# IO.net
KiCad netlist of a schematic drawn in Altium Designer
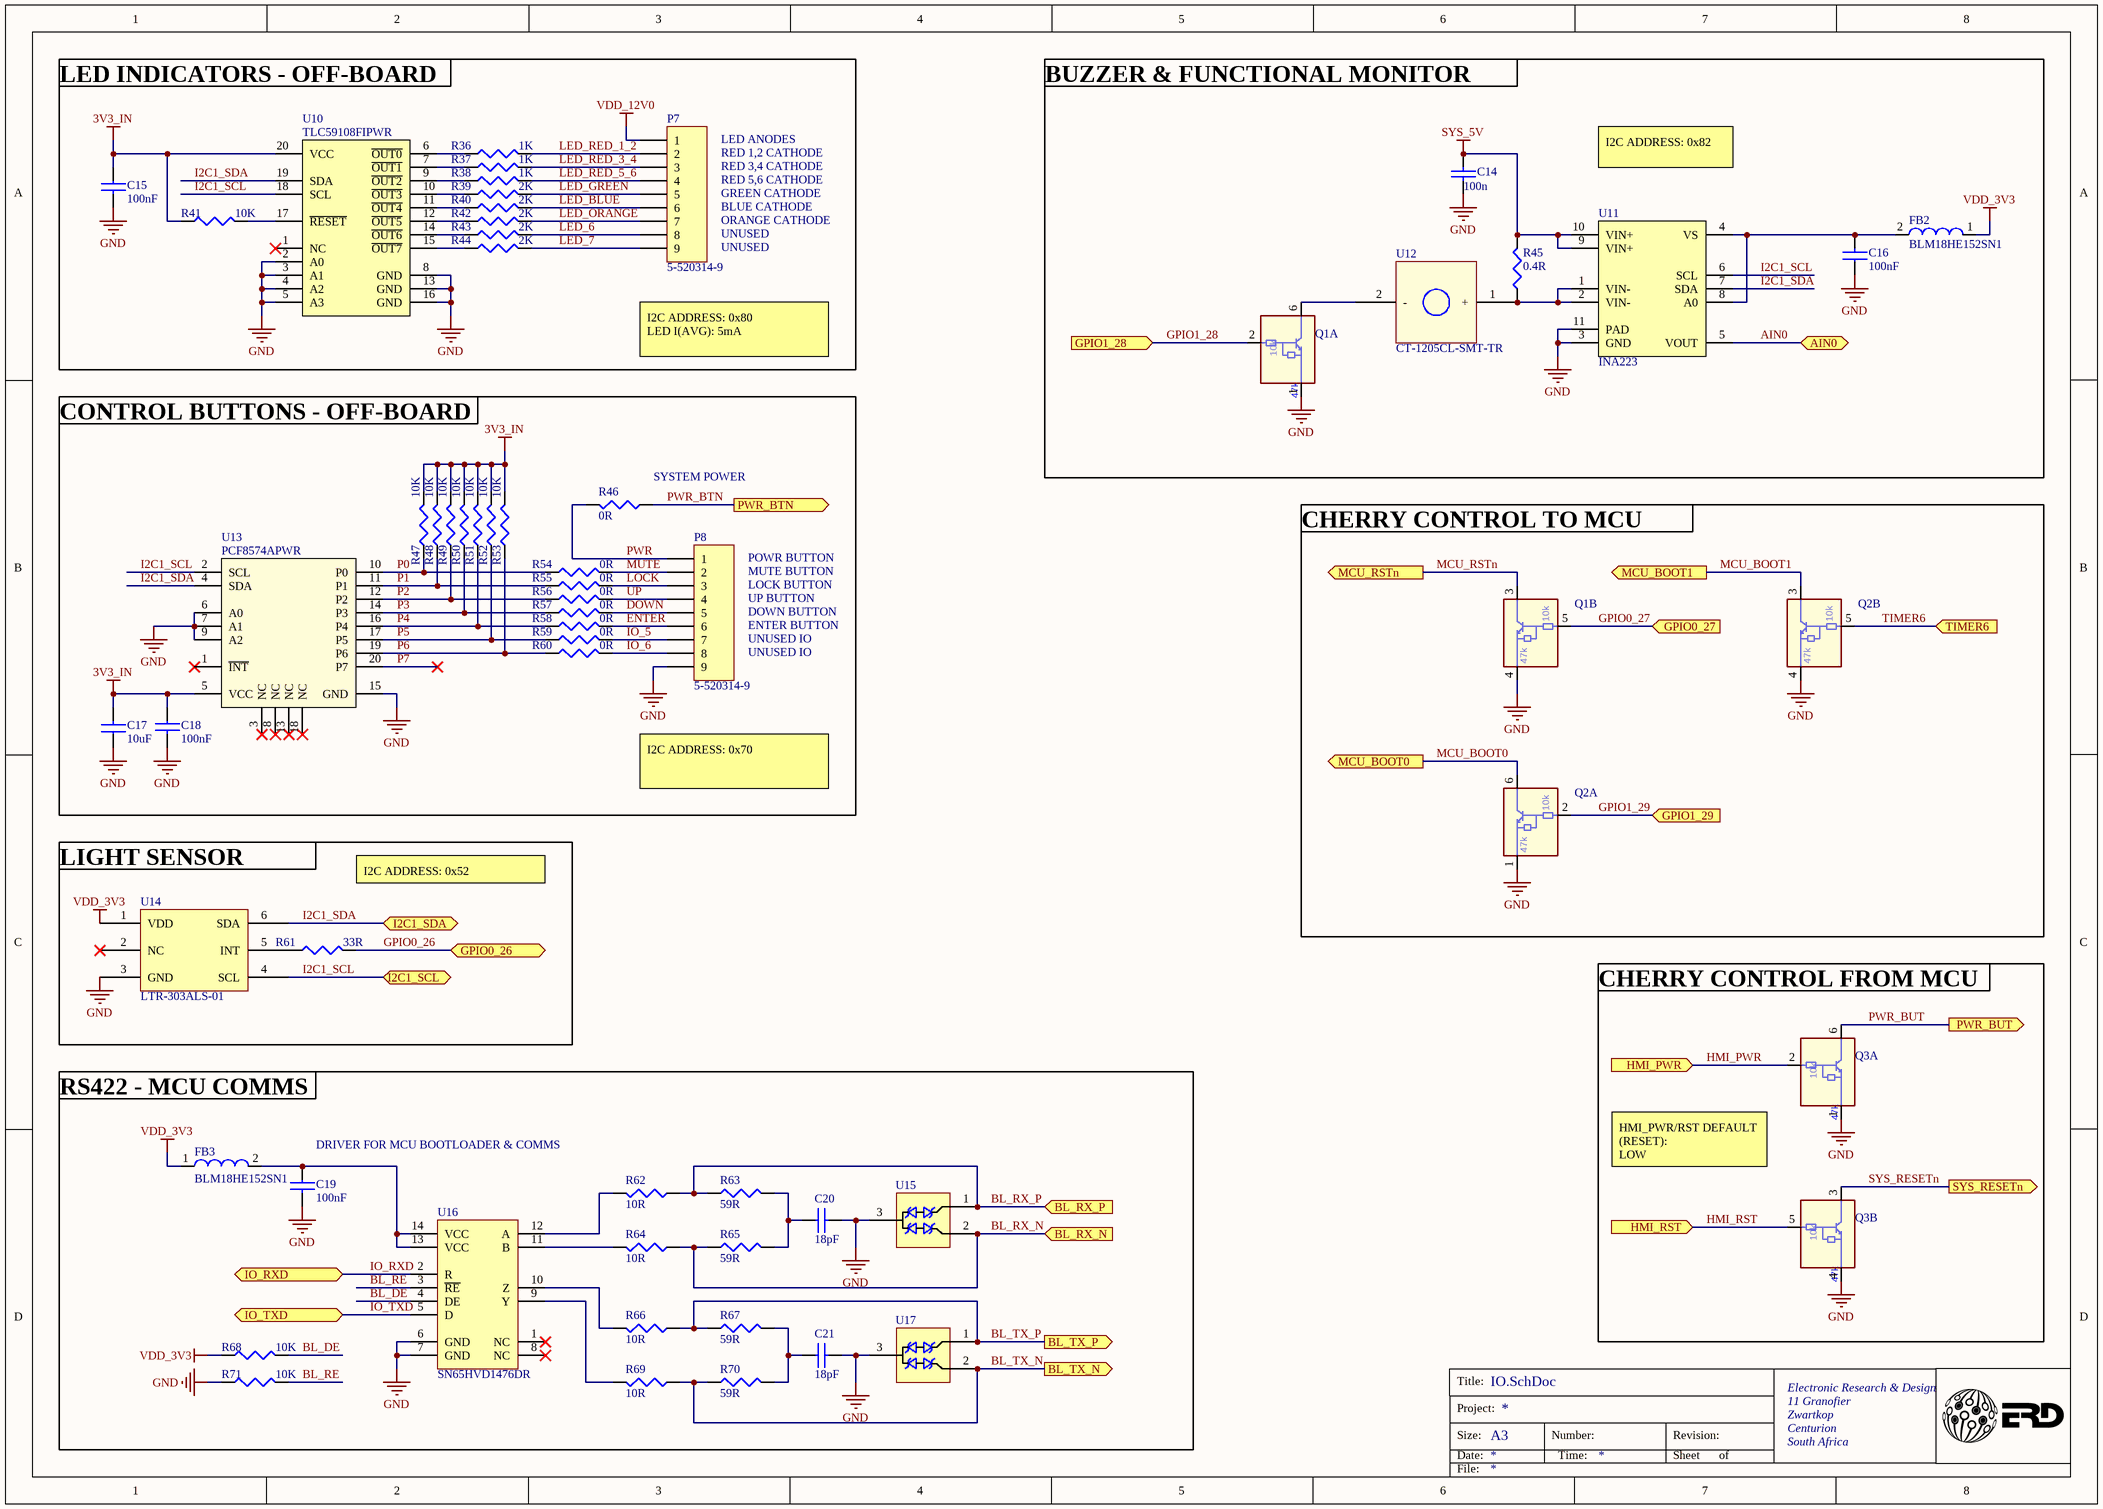
[diagram p0: IO.SchDoc]

(export (version "E")
  (design (tool "Eeschema 10.0.6"))
  (components
    (comp (ref "C14")
      (value "100nF")
      (footprint "CC0402")
      (description "Capacitor, Ceramic")
      (fields
        (field (name "TOLERANCE") "±20%")
        (field (name "VOLTAGE") "25V")
        (field (name "COMMENT_1") "100n")
      )
      (libsource (lib "*") (part "CAPCERAMIC"))
    )
    (comp (ref "C15")
      (value "100nF")
      (footprint "CC0402")
      (description "CAP CER 0.1UF 50V 10% X7R 0402")
      (fields (field (name "MANUFACTURER") "Murata") (field (name "PARTNUMBER") "GCM155R71H104KE02D"))
      (libsource (lib "ERD TiAm") (part "CAP CER 0.1UF 10V 10% X5R 0402"))
    )
    (comp (ref "C16")
      (value "100nF")
      (footprint "CC0402")
      (description "CAP CER 0.1UF 50V 10% X7R 0402")
      (fields (field (name "MANUFACTURER") "Murata") (field (name "PARTNUMBER") "GCM155R71H104KE02D"))
      (libsource (lib "ERD TiAm") (part "CAP CER 0.1UF 10V 10% X5R 0402"))
    )
    (comp (ref "C17")
      (value "10uF")
      (footprint "CC0603")
      (description "CAP CER 10UF 25V 20% X5R 0603")
      (fields (field (name "MANUFACTURER") "Murata") (field (name "PARTNUMBER") "GRM188R61E106MA73D"))
      (libsource (lib "ERD TiAm") (part "CAP CER 0.1UF 10V 10% X5R 0402"))
    )
    (comp (ref "C18")
      (value "100nF")
      (footprint "CC0402")
      (description "CAP CER 0.1UF 50V 10% X7R 0402")
      (fields (field (name "MANUFACTURER") "Murata") (field (name "PARTNUMBER") "GCM155R71H104KE02D"))
      (libsource (lib "ERD TiAm") (part "CAP CER 0.1UF 10V 10% X5R 0402"))
    )
    (comp (ref "C19")
      (value "100nF")
      (footprint "CC0402")
      (description "CAP CER 0.1UF 50V 10% X7R 0402")
      (fields (field (name "MANUFACTURER") "Murata") (field (name "PARTNUMBER") "GCM155R71H104KE02D"))
      (libsource (lib "ERD TiAm") (part "CAP CER 0.1UF 10V 10% X5R 0402"))
    )
    (comp (ref "C20")
      (value "18pF")
      (footprint "CC0402")
      (description "CAP CER 18pF 50V 5% C0G 0402")
      (fields (field (name "MANUFACTURER") "AVX") (field (name "PARTNUMBER") "GJM1555C1H180FB01D"))
      (libsource (lib "ERD TiAm") (part "CAP CER 2.2UF 6.3V 10% X5R 0402"))
    )
    (comp (ref "C21")
      (value "18pF")
      (footprint "CC0402")
      (description "CAP CER 18pF 50V 5% C0G 0402")
      (fields (field (name "MANUFACTURER") "AVX") (field (name "PARTNUMBER") "GJM1555C1H180FB01D"))
      (libsource (lib "ERD TiAm") (part "CAP CER 2.2UF 6.3V 10% X5R 0402"))
    )
    (comp (ref "FB2")
      (value "BLM18HE152SN1")
      (footprint "LC0603")
      (description "FERRITE, 500mA, 500mOHM, 0603")
      (libsource (lib "") (part "FER_180_200_0_1"))
    )
    (comp (ref "FB3")
      (value "BLM18HE152SN1")
      (footprint "LC0603")
      (description "FERRITE, 500mA, 500mOHM, 0603")
      (libsource (lib "BEAGLEBONEBLACK_REV A5B") (part "FER_180_200_0"))
    )
    (comp (ref "P7")
      (value "5-520314-9")
      (footprint "HDR1X9")
      (description "FPC Connector, 9-circuit, 2.54mm pitch, RA, TH")
      (fields (field (name "MANUFACTURER") "TE"))
      (libsource (lib "Miscellaneous Connectors") (part "Header 9"))
    )
    (comp (ref "P8")
      (value "5-520314-9")
      (footprint "HDR1X9")
      (description "FPC Connector, 9-circuit, 2.54mm pitch, RA, TH")
      (fields (field (name "MANUFACTURER") "TE"))
      (libsource (lib "Miscellaneous Connectors") (part "Header 9"))
    )
    (comp (ref "Q1")
      (value "DDC114YU-7-F")
      (description "TRANS PREBIASED DUAL NPN SOT363")
      (fields (field (name "MANUFACTURER") "Diodes Inc"))
      (libsource (lib "ERD TiAm") (part "RN1907"))
    )
    (comp (ref "Q2")
      (value "DDC114YU-7-F")
      (description "TRANS PREBIASED DUAL NPN SOT363")
      (fields (field (name "MANUFACTURER") "Diodes Inc"))
      (libsource (lib "ERD TiAm") (part "RN1907"))
    )
    (comp (ref "Q3")
      (value "DDC114YU-7-F")
      (description "TRANS PREBIASED DUAL NPN SOT363")
      (fields (field (name "MANUFACTURER") "Diodes Inc"))
      (libsource (lib "") (part "RN1907_1"))
    )
    (comp (ref "R36")
      (value "1K")
      (footprint "RC0402")
      (description "RES, 1K OHM, 1/16W, 1%, 0402")
      (fields (field (name "MANUFACTURER") "Yageo") (field (name "PARTNUMBER") "RC0402FR-071KL"))
      (libsource (lib "ERD TiAm") (part "RES_10K_1/16W_1%_0402"))
    )
    (comp (ref "R37")
      (value "1K")
      (footprint "RC0402")
      (description "RES, 1K OHM, 1/16W, 1%, 0402")
      (fields (field (name "MANUFACTURER") "Yageo") (field (name "PARTNUMBER") "RC0402FR-071KL"))
      (libsource (lib "ERD TiAm") (part "RES_10K_1/16W_1%_0402"))
    )
    (comp (ref "R38")
      (value "1K")
      (footprint "RC0402")
      (description "RES, 1K OHM, 1/16W, 1%, 0402")
      (fields (field (name "MANUFACTURER") "Yageo") (field (name "PARTNUMBER") "RC0402FR-071KL"))
      (libsource (lib "ERD TiAm") (part "RES_10K_1/16W_1%_0402"))
    )
    (comp (ref "R39")
      (value "2K")
      (footprint "RC0402")
      (description "RES, 2K OHM, 1/16W, 1%, 0402")
      (fields (field (name "MANUFACTURER") "Yageo") (field (name "PARTNUMBER") "RC0402FR-072KL"))
      (libsource (lib "ERD TiAm") (part "RES_10K_1/16W_1%_0402"))
    )
    (comp (ref "R40")
      (value "2K")
      (footprint "RC0402")
      (description "RES, 2K OHM, 1/16W, 1%, 0402")
      (fields (field (name "MANUFACTURER") "Yageo") (field (name "PARTNUMBER") "RC0402FR-072KL"))
      (libsource (lib "ERD TiAm") (part "RES_10K_1/16W_1%_0402"))
    )
    (comp (ref "R41")
      (value "10K")
      (footprint "RC0402")
      (description "RES, 10K OHM, 1/16W, 1%, 0402")
      (fields (field (name "MANUFACTURER") "Yageo") (field (name "PART NUMBER") "RC0402FR-0710KL"))
      (libsource (lib "ERD TiAm") (part "RES_10K_1/16W_1%_0402"))
    )
    (comp (ref "R42")
      (value "2K")
      (footprint "RC0402")
      (description "RES, 2K OHM, 1/16W, 1%, 0402")
      (fields (field (name "MANUFACTURER") "Yageo") (field (name "PARTNUMBER") "RC0402FR-072KL"))
      (libsource (lib "ERD TiAm") (part "RES_10K_1/16W_1%_0402"))
    )
    (comp (ref "R43")
      (value "2K")
      (footprint "RC0402")
      (description "RES, 2K OHM, 1/16W, 1%, 0402")
      (fields (field (name "MANUFACTURER") "Yageo") (field (name "PARTNUMBER") "RC0402FR-072KL"))
      (libsource (lib "ERD TiAm") (part "RES_10K_1/16W_1%_0402"))
    )
    (comp (ref "R44")
      (value "2K")
      (footprint "RC0402")
      (description "RES, 2K OHM, 1/16W, 1%, 0402")
      (fields (field (name "MANUFACTURER") "Yageo") (field (name "PARTNUMBER") "RC0402FR-072KL"))
      (libsource (lib "ERD TiAm") (part "RES_10K_1/16W_1%_0402"))
    )
    (comp (ref "R45")
      (value "0.4R")
      (footprint "RC1210")
      (description "RES, 0.4 OHM, 1/2W, 1%, 2010")
      (fields (field (name "MANUFACTURER") "Yageo") (field (name "PARTNUMBER") "WSL2010R4000FEA"))
      (libsource (lib "ERD TiAm") (part "RES_10K_1/16W_1%_0402"))
    )
    (comp (ref "R46")
      (value "0R")
      (footprint "RC0402")
      (description "RES, 0 OHM, 1/16W, 1%, 0402")
      (fields (field (name "MANUFACTURER") "Yageo") (field (name "PARTNUMBER") "RC0402FR-070RL"))
      (libsource (lib "ERD TiAm") (part "RES_10K_1/16W_1%_0402"))
    )
    (comp (ref "R47")
      (value "10K")
      (footprint "RC0402")
      (description "RES, 10K OHM, 1/16W, 1%, 0402")
      (fields (field (name "MANUFACTURER") "Yageo") (field (name "PARTNUMBER") "RC0402FR-0710KL"))
      (libsource (lib "ERD TiAm") (part "RES_10K_1/16W_1%_0402"))
    )
    (comp (ref "R48")
      (value "10K")
      (footprint "RC0402")
      (description "RES, 10K OHM, 1/16W, 1%, 0402")
      (fields (field (name "MANUFACTURER") "Yageo") (field (name "PARTNUMBER") "RC0402FR-0710KL"))
      (libsource (lib "ERD TiAm") (part "RES_10K_1/16W_1%_0402"))
    )
    (comp (ref "R49")
      (value "10K")
      (footprint "RC0402")
      (description "RES, 10K OHM, 1/16W, 1%, 0402")
      (fields (field (name "MANUFACTURER") "Yageo") (field (name "PARTNUMBER") "RC0402FR-0710KL"))
      (libsource (lib "ERD TiAm") (part "RES_10K_1/16W_1%_0402"))
    )
    (comp (ref "R50")
      (value "10K")
      (footprint "RC0402")
      (description "RES, 10K OHM, 1/16W, 1%, 0402")
      (fields (field (name "MANUFACTURER") "Yageo") (field (name "PARTNUMBER") "RC0402FR-0710KL"))
      (libsource (lib "ERD TiAm") (part "RES_10K_1/16W_1%_0402"))
    )
    (comp (ref "R51")
      (value "10K")
      (footprint "RC0402")
      (description "RES, 10K OHM, 1/16W, 1%, 0402")
      (fields (field (name "MANUFACTURER") "Yageo") (field (name "PARTNUMBER") "RC0402FR-0710KL"))
      (libsource (lib "ERD TiAm") (part "RES_10K_1/16W_1%_0402"))
    )
    (comp (ref "R52")
      (value "10K")
      (footprint "RC0402")
      (description "RES, 10K OHM, 1/16W, 1%, 0402")
      (fields (field (name "MANUFACTURER") "Yageo") (field (name "PARTNUMBER") "RC0402FR-0710KL"))
      (libsource (lib "ERD TiAm") (part "RES_10K_1/16W_1%_0402"))
    )
    (comp (ref "R53")
      (value "10K")
      (footprint "RC0402")
      (description "RES, 10K OHM, 1/16W, 1%, 0402")
      (fields (field (name "MANUFACTURER") "Yageo") (field (name "PARTNUMBER") "RC0402FR-0710KL"))
      (libsource (lib "ERD TiAm") (part "RES_10K_1/16W_1%_0402"))
    )
    (comp (ref "R54")
      (value "0R")
      (footprint "RC0402")
      (description "RES, 0 OHM, 1/16W, 1%, 0402")
      (fields (field (name "MANUFACTURER") "Yageo") (field (name "PARTNUMBER") "RC0402FR-070RL"))
      (libsource (lib "ERD TiAm") (part "RES_10K_1/16W_1%_0402"))
    )
    (comp (ref "R55")
      (value "0R")
      (footprint "RC0402")
      (description "RES, 0 OHM, 1/16W, 1%, 0402")
      (fields (field (name "MANUFACTURER") "Yageo") (field (name "PARTNUMBER") "RC0402FR-070RL"))
      (libsource (lib "ERD TiAm") (part "RES_10K_1/16W_1%_0402"))
    )
    (comp (ref "R56")
      (value "0R")
      (footprint "RC0402")
      (description "RES, 0 OHM, 1/16W, 1%, 0402")
      (fields (field (name "MANUFACTURER") "Yageo") (field (name "PARTNUMBER") "RC0402FR-070RL"))
      (libsource (lib "ERD TiAm") (part "RES_10K_1/16W_1%_0402"))
    )
    (comp (ref "R57")
      (value "0R")
      (footprint "RC0402")
      (description "RES, 0 OHM, 1/16W, 1%, 0402")
      (fields (field (name "MANUFACTURER") "Yageo") (field (name "PARTNUMBER") "RC0402FR-070RL"))
      (libsource (lib "ERD TiAm") (part "RES_10K_1/16W_1%_0402"))
    )
    (comp (ref "R58")
      (value "0R")
      (footprint "RC0402")
      (description "RES, 0 OHM, 1/16W, 1%, 0402")
      (fields (field (name "MANUFACTURER") "Yageo") (field (name "PARTNUMBER") "RC0402FR-070RL"))
      (libsource (lib "ERD TiAm") (part "RES_10K_1/16W_1%_0402"))
    )
    (comp (ref "R59")
      (value "0R")
      (footprint "RC0402")
      (description "RES, 0 OHM, 1/16W, 1%, 0402")
      (fields (field (name "MANUFACTURER") "Yageo") (field (name "PARTNUMBER") "RC0402FR-070RL"))
      (libsource (lib "ERD TiAm") (part "RES_10K_1/16W_1%_0402"))
    )
    (comp (ref "R60")
      (value "0R")
      (footprint "RC0402")
      (description "RES, 0 OHM, 1/16W, 1%, 0402")
      (fields (field (name "MANUFACTURER") "Yageo") (field (name "PARTNUMBER") "RC0402FR-070RL"))
      (libsource (lib "ERD TiAm") (part "RES_10K_1/16W_1%_0402"))
    )
    (comp (ref "R61")
      (value "33R")
      (footprint "RC0402")
      (description "RES, 33 OHM, 1/16W, 1%, 0402")
      (fields (field (name "MANUFACTURER") "Yageo") (field (name "PARTNUMBER") "RC0402FR-0733RL"))
      (libsource (lib "ERD TiAm") (part "RES_10K_1/16W_1%_0402"))
    )
    (comp (ref "R62")
      (value "10R")
      (footprint "RC0603")
      (description "RES 10 OHM 1/10W 5% 0603 SMD")
      (fields (field (name "MANUFACTURER") "Yageo") (field (name "PARTNUMBER") "RC0603JR-0710RL"))
      (libsource (lib "ERD TiAm") (part "RES_10K_1/16W_1%_0402"))
    )
    (comp (ref "R63")
      (value "59R")
      (footprint "RC0402")
      (description "RES, 59 OHM, 1/16W, 1%, 0402")
      (fields (field (name "MANUFACTURER") "Yageo") (field (name "PARTNUMBER") "RC0402FR-0759RL"))
      (libsource (lib "ERD TiAm") (part "RES_10K_1/16W_1%_0402"))
    )
    (comp (ref "R64")
      (value "10R")
      (footprint "RC0603")
      (description "RES 10 OHM 1/10W 5% 0603 SMD")
      (fields (field (name "MANUFACTURER") "Yageo") (field (name "PARTNUMBER") "RC0603JR-0710RL"))
      (libsource (lib "ERD TiAm") (part "RES_10K_1/16W_1%_0402"))
    )
    (comp (ref "R65")
      (value "59R")
      (footprint "RC0402")
      (description "RES, 59 OHM, 1/16W, 1%, 0402")
      (fields (field (name "MANUFACTURER") "Yageo") (field (name "PARTNUMBER") "RC0402FR-0759RL"))
      (libsource (lib "ERD TiAm") (part "RES_10K_1/16W_1%_0402"))
    )
    (comp (ref "R66")
      (value "10R")
      (footprint "RC0603")
      (description "RES 10 OHM 1/10W 5% 0603 SMD")
      (fields (field (name "MANUFACTURER") "Yageo") (field (name "PARTNUMBER") "RC0603JR-0710RL"))
      (libsource (lib "ERD TiAm") (part "RES_10K_1/16W_1%_0402"))
    )
    (comp (ref "R67")
      (value "59R")
      (footprint "RC0402")
      (description "RES, 59 OHM, 1/16W, 1%, 0402")
      (fields (field (name "MANUFACTURER") "Yageo") (field (name "PARTNUMBER") "RC0402FR-0759RL"))
      (libsource (lib "ERD TiAm") (part "RES_10K_1/16W_1%_0402"))
    )
    (comp (ref "R68")
      (value "10K")
      (footprint "RC0402")
      (description "RES, 10K OHM, 1/16W, 1%, 0402")
      (fields (field (name "MANUFACTURER") "Yageo") (field (name "PART NUMBER") "RC0402FR-0710KL"))
      (libsource (lib "ERD TiAm") (part "RES_10K_1/16W_1%_0402"))
    )
    (comp (ref "R69")
      (value "10R")
      (footprint "RC0603")
      (description "RES 10 OHM 1/10W 5% 0603 SMD")
      (fields (field (name "MANUFACTURER") "Yageo") (field (name "PARTNUMBER") "RC0603JR-0710RL"))
      (libsource (lib "ERD TiAm") (part "RES_10K_1/16W_1%_0402"))
    )
    (comp (ref "R70")
      (value "59R")
      (footprint "RC0402")
      (description "RES, 59 OHM, 1/16W, 1%, 0402")
      (fields (field (name "MANUFACTURER") "Yageo") (field (name "PARTNUMBER") "RC0402FR-0759RL"))
      (libsource (lib "ERD TiAm") (part "RES_10K_1/16W_1%_0402"))
    )
    (comp (ref "R71")
      (value "10K")
      (footprint "RC0402")
      (description "RES, 10K OHM, 1/16W, 1%, 0402")
      (fields (field (name "MANUFACTURER") "Yageo") (field (name "PART NUMBER") "RC0402FR-0710KL"))
      (libsource (lib "ERD TiAm") (part "RES_10K_1/16W_1%_0402"))
    )
    (comp (ref "U10")
      (value "TLC59108FIPWR")
      (footprint "TSSOP-20")
      (description "LED Driver, 8-Channel, I2C, TSSOP-20")
      (libsource (lib "ERD TiAm") (part "TLC59108F"))
    )
    (comp (ref "U11")
      (value "INA223")
      (description "Power Monitor, I2C, SON-10")
      (libsource (lib "ERD TiAm") (part "INA223"))
    )
    (comp (ref "U12")
      (value "CT-1205CL-SMT-TR")
      (description "CUI CT-1205CL-SMT-TR Buzzer")
      (libsource (lib "CONNECTORS") (part "CT-1205CL-SMT"))
    )
    (comp (ref "U13")
      (value "PCF8574APWR")
      (footprint "ERD TiAm:TSSOP-20")
      (description "IO Expander, I2C, 8-bit, TSSOP-20")
      (fields (field (name "MANUFACTURER") "Texas Instruments"))
      (libsource (lib "ERD TiAm") (part "PCF8574APWR"))
    )
    (comp (ref "U14")
      (value "LTR-303ALS-01")
      (footprint "LTR-303")
      (description "LIGHT SENSOR")
      (libsource (lib "BCI_rev_0") (part "LTR-303ALS-01"))
    )
    (comp (ref "U15")
      (value "TPD2E007DCKR")
      (footprint "SOT23 - DGK")
      (description "DIODE, TVS, 2-CHANNEL ESD PROTECTION ARRAY, SOT23")
      (fields (field (name "MANUFACTURER") "Texas Instruments"))
      (libsource (lib "ERD TiAm") (part "TPD2E007"))
    )
    (comp (ref "U16")
      (value "SN65HVD1476DR")
      (footprint "SOIC-14")
      (description "Transceiver, RS-485/422, Full-Duplex, SOIC-14")
      (libsource (lib "ERD TiAm") (part "SN65HVD1476"))
    )
    (comp (ref "U17")
      (value "TPD2E007DCKR")
      (footprint "SOT23 - DGK")
      (description "DIODE, TVS, 2-CHANNEL ESD PROTECTION ARRAY, SOT23")
      (fields (field (name "MANUFACTURER") "Texas Instruments"))
      (libsource (lib "ERD TiAm") (part "TPD2E007"))
    )
  )
  (nets
    (net (code "1") (name "/AIN0") (class "Default")
      (node (ref "U11") (pin "5") (pinfunction "VOUT_5") (pintype "passive"))
    )
    (net (code "2") (name "/BL_DE") (class "Default")
      (node (ref "R68") (pin "2") (pinfunction "2_2") (pintype "passive"))
      (node (ref "U16") (pin "4") (pinfunction "DE_4") (pintype "passive"))
    )
    (net (code "3") (name "/BL_RE") (class "Default")
      (node (ref "R71") (pin "2") (pinfunction "2_2") (pintype "passive"))
      (node (ref "U16") (pin "3") (pinfunction "~{RE}_3") (pintype "passive"))
    )
    (net (code "4") (name "/BL_RX_N") (class "Default")
      (node (ref "R64") (pin "1") (pinfunction "1_1") (pintype "passive"))
      (node (ref "R65") (pin "1") (pinfunction "1_1") (pintype "passive"))
      (node (ref "U15") (pin "2") (pinfunction "IO2_2") (pintype "passive"))
    )
    (net (code "5") (name "/BL_RX_P") (class "Default")
      (node (ref "R62") (pin "1") (pinfunction "1_1") (pintype "passive"))
      (node (ref "R63") (pin "1") (pinfunction "1_1") (pintype "passive"))
      (node (ref "U15") (pin "1") (pinfunction "IO1_1") (pintype "passive"))
    )
    (net (code "6") (name "/BL_TX_N") (class "Default")
      (node (ref "R69") (pin "1") (pinfunction "1_1") (pintype "passive"))
      (node (ref "R70") (pin "1") (pinfunction "1_1") (pintype "passive"))
      (node (ref "U17") (pin "2") (pinfunction "IO2_2") (pintype "passive"))
    )
    (net (code "7") (name "/BL_TX_P") (class "Default")
      (node (ref "R66") (pin "1") (pinfunction "1_1") (pintype "passive"))
      (node (ref "R67") (pin "1") (pinfunction "1_1") (pintype "passive"))
      (node (ref "U17") (pin "1") (pinfunction "IO1_1") (pintype "passive"))
    )
    (net (code "8") (name "/DOWN") (class "Default")
      (node (ref "P8") (pin "5") (pinfunction "5_5") (pintype "passive"))
      (node (ref "R57") (pin "2") (pinfunction "2_2") (pintype "passive"))
    )
    (net (code "9") (name "/ENTER") (class "Default")
      (node (ref "P8") (pin "6") (pinfunction "6_6") (pintype "passive"))
      (node (ref "R58") (pin "2") (pinfunction "2_2") (pintype "passive"))
    )
    (net (code "10") (name "/GPIO0_26") (class "Default")
      (node (ref "R61") (pin "2") (pinfunction "2_2") (pintype "passive"))
    )
    (net (code "11") (name "/GPIO0_27") (class "Default")
      (node (ref "Q1") (pin "5") (pinfunction "5_5") (pintype "passive"))
    )
    (net (code "12") (name "/GPIO1_28") (class "Default")
      (node (ref "Q1") (pin "2") (pinfunction "5_2") (pintype "passive"))
    )
    (net (code "13") (name "/GPIO1_29") (class "Default")
      (node (ref "Q2") (pin "2") (pinfunction "5_2") (pintype "passive"))
    )
    (net (code "14") (name "/HMI_PWR") (class "Default")
      (node (ref "Q3") (pin "2") (pinfunction "5_2") (pintype "passive"))
    )
    (net (code "15") (name "/HMI_RST") (class "Default")
      (node (ref "Q3") (pin "5") (pinfunction "5_5") (pintype "passive"))
    )
    (net (code "16") (name "/I2C1_SCL") (class "Default")
      (node (ref "U10") (pin "18") (pinfunction "SCL_18") (pintype "passive"))
      (node (ref "U11") (pin "6") (pinfunction "SCL_6") (pintype "passive"))
      (node (ref "U13") (pin "2") (pinfunction "SCL_2") (pintype "passive"))
      (node (ref "U14") (pin "4") (pinfunction "SCL_4") (pintype "passive"))
    )
    (net (code "17") (name "/I2C1_SDA") (class "Default")
      (node (ref "U10") (pin "19") (pinfunction "SDA_19") (pintype "passive"))
      (node (ref "U11") (pin "7") (pinfunction "SDA_7") (pintype "passive"))
      (node (ref "U13") (pin "4") (pinfunction "SDA_4") (pintype "passive"))
      (node (ref "U14") (pin "6") (pinfunction "SDA_6") (pintype "passive"))
    )
    (net (code "18") (name "/IO_5") (class "Default")
      (node (ref "P8") (pin "7") (pinfunction "7_7") (pintype "passive"))
      (node (ref "R59") (pin "2") (pinfunction "2_2") (pintype "passive"))
    )
    (net (code "19") (name "/IO_6") (class "Default")
      (node (ref "P8") (pin "8") (pinfunction "8_8") (pintype "passive"))
      (node (ref "R60") (pin "2") (pinfunction "2_2") (pintype "passive"))
    )
    (net (code "20") (name "/IO_RXD") (class "Default")
      (node (ref "U16") (pin "2") (pinfunction "R_2") (pintype "passive"))
    )
    (net (code "21") (name "/IO_TXD") (class "Default")
      (node (ref "U16") (pin "5") (pinfunction "D_5") (pintype "passive"))
    )
    (net (code "22") (name "/LED_6") (class "Default")
      (node (ref "P7") (pin "8") (pinfunction "8_8") (pintype "passive"))
      (node (ref "R43") (pin "2") (pinfunction "2_2") (pintype "passive"))
    )
    (net (code "23") (name "/LED_7") (class "Default")
      (node (ref "P7") (pin "9") (pinfunction "9_9") (pintype "passive"))
      (node (ref "R44") (pin "2") (pinfunction "2_2") (pintype "passive"))
    )
    (net (code "24") (name "/LED_BLUE") (class "Default")
      (node (ref "P7") (pin "6") (pinfunction "6_6") (pintype "passive"))
      (node (ref "R40") (pin "2") (pinfunction "2_2") (pintype "passive"))
    )
    (net (code "25") (name "/LED_GREEN") (class "Default")
      (node (ref "P7") (pin "5") (pinfunction "5_5") (pintype "passive"))
      (node (ref "R39") (pin "2") (pinfunction "2_2") (pintype "passive"))
    )
    (net (code "26") (name "/LED_ORANGE") (class "Default")
      (node (ref "P7") (pin "7") (pinfunction "7_7") (pintype "passive"))
      (node (ref "R42") (pin "2") (pinfunction "2_2") (pintype "passive"))
    )
    (net (code "27") (name "/LED_RED_1_2") (class "Default")
      (node (ref "P7") (pin "2") (pinfunction "2_2") (pintype "passive"))
      (node (ref "R36") (pin "2") (pinfunction "2_2") (pintype "passive"))
    )
    (net (code "28") (name "/LED_RED_3_4") (class "Default")
      (node (ref "P7") (pin "3") (pinfunction "3_3") (pintype "passive"))
      (node (ref "R37") (pin "2") (pinfunction "2_2") (pintype "passive"))
    )
    (net (code "29") (name "/LED_RED_5_6") (class "Default")
      (node (ref "P7") (pin "4") (pinfunction "4_4") (pintype "passive"))
      (node (ref "R38") (pin "2") (pinfunction "2_2") (pintype "passive"))
    )
    (net (code "30") (name "/LOCK") (class "Default")
      (node (ref "P8") (pin "3") (pinfunction "3_3") (pintype "passive"))
      (node (ref "R55") (pin "2") (pinfunction "2_2") (pintype "passive"))
    )
    (net (code "31") (name "/MCU_BOOT0") (class "Default")
      (node (ref "Q2") (pin "6") (pinfunction "3_6") (pintype "passive"))
    )
    (net (code "32") (name "/MCU_BOOT1") (class "Default")
      (node (ref "Q2") (pin "3") (pinfunction "3_3") (pintype "passive"))
    )
    (net (code "33") (name "/MCU_RSTn") (class "Default")
      (node (ref "Q1") (pin "3") (pinfunction "3_3") (pintype "passive"))
    )
    (net (code "34") (name "/MUTE") (class "Default")
      (node (ref "P8") (pin "2") (pinfunction "2_2") (pintype "passive"))
      (node (ref "R54") (pin "2") (pinfunction "2_2") (pintype "passive"))
    )
    (net (code "35") (name "/P0") (class "Default")
      (node (ref "R47") (pin "1") (pinfunction "1_1") (pintype "passive"))
      (node (ref "R54") (pin "1") (pinfunction "1_1") (pintype "passive"))
      (node (ref "U13") (pin "10") (pinfunction "P0_10") (pintype "passive"))
    )
    (net (code "36") (name "/P1") (class "Default")
      (node (ref "R48") (pin "1") (pinfunction "1_1") (pintype "passive"))
      (node (ref "R55") (pin "1") (pinfunction "1_1") (pintype "passive"))
      (node (ref "U13") (pin "11") (pinfunction "P1_11") (pintype "passive"))
    )
    (net (code "37") (name "/P2") (class "Default")
      (node (ref "R49") (pin "1") (pinfunction "1_1") (pintype "passive"))
      (node (ref "R56") (pin "1") (pinfunction "1_1") (pintype "passive"))
      (node (ref "U13") (pin "12") (pinfunction "P2_12") (pintype "passive"))
    )
    (net (code "38") (name "/P3") (class "Default")
      (node (ref "R50") (pin "1") (pinfunction "1_1") (pintype "passive"))
      (node (ref "R57") (pin "1") (pinfunction "1_1") (pintype "passive"))
      (node (ref "U13") (pin "14") (pinfunction "P3_14") (pintype "passive"))
    )
    (net (code "39") (name "/P4") (class "Default")
      (node (ref "R51") (pin "1") (pinfunction "1_1") (pintype "passive"))
      (node (ref "R58") (pin "1") (pinfunction "1_1") (pintype "passive"))
      (node (ref "U13") (pin "16") (pinfunction "P4_16") (pintype "passive"))
    )
    (net (code "40") (name "/P5") (class "Default")
      (node (ref "R52") (pin "1") (pinfunction "1_1") (pintype "passive"))
      (node (ref "R59") (pin "1") (pinfunction "1_1") (pintype "passive"))
      (node (ref "U13") (pin "17") (pinfunction "P5_17") (pintype "passive"))
    )
    (net (code "41") (name "/P6") (class "Default")
      (node (ref "R53") (pin "1") (pinfunction "1_1") (pintype "passive"))
      (node (ref "R60") (pin "1") (pinfunction "1_1") (pintype "passive"))
      (node (ref "U13") (pin "19") (pinfunction "P6_19") (pintype "passive"))
    )
    (net (code "42") (name "/P7") (class "Default")
      (node (ref "U13") (pin "20") (pinfunction "P7_20") (pintype "passive+no_connect"))
    )
    (net (code "43") (name "/PWR") (class "Default")
      (node (ref "P8") (pin "1") (pinfunction "1_1") (pintype "passive"))
      (node (ref "R46") (pin "2") (pinfunction "2_2") (pintype "passive"))
    )
    (net (code "44") (name "/PWR_BTN") (class "Default")
      (node (ref "R46") (pin "1") (pinfunction "1_1") (pintype "passive"))
    )
    (net (code "45") (name "/PWR_BUT") (class "Default")
      (node (ref "Q3") (pin "6") (pinfunction "3_6") (pintype "passive"))
    )
    (net (code "46") (name "/SYS_RESETn") (class "Default")
      (node (ref "Q3") (pin "3") (pinfunction "3_3") (pintype "passive"))
    )
    (net (code "47") (name "/TIMER6") (class "Default")
      (node (ref "Q2") (pin "5") (pinfunction "5_5") (pintype "passive"))
    )
    (net (code "48") (name "/UP") (class "Default")
      (node (ref "P8") (pin "4") (pinfunction "4_4") (pintype "passive"))
      (node (ref "R56") (pin "2") (pinfunction "2_2") (pintype "passive"))
    )
    (net (code "49") (name "3V3_IN") (class "Default")
      (node (ref "C15") (pin "1") (pinfunction "1_1") (pintype "passive"))
      (node (ref "C17") (pin "2") (pinfunction "2_2") (pintype "passive"))
      (node (ref "C18") (pin "1") (pinfunction "1_1") (pintype "passive"))
      (node (ref "R41") (pin "1") (pinfunction "1_1") (pintype "passive"))
      (node (ref "R47") (pin "2") (pinfunction "2_2") (pintype "passive"))
      (node (ref "R48") (pin "2") (pinfunction "2_2") (pintype "passive"))
      (node (ref "R49") (pin "2") (pinfunction "2_2") (pintype "passive"))
      (node (ref "R50") (pin "2") (pinfunction "2_2") (pintype "passive"))
      (node (ref "R51") (pin "2") (pinfunction "2_2") (pintype "passive"))
      (node (ref "R52") (pin "2") (pinfunction "2_2") (pintype "passive"))
      (node (ref "R53") (pin "2") (pinfunction "2_2") (pintype "passive"))
      (node (ref "U10") (pin "20") (pinfunction "VCC_20") (pintype "passive"))
      (node (ref "U13") (pin "5") (pinfunction "VCC_5") (pintype "passive"))
    )
    (net (code "50") (name "GND") (class "Default")
      (node (ref "C14") (pin "1") (pintype "passive"))
      (node (ref "C15") (pin "2") (pinfunction "2_2") (pintype "passive"))
      (node (ref "C16") (pin "1") (pinfunction "1_1") (pintype "passive"))
      (node (ref "C17") (pin "1") (pinfunction "1_1") (pintype "passive"))
      (node (ref "C18") (pin "2") (pinfunction "2_2") (pintype "passive"))
      (node (ref "C19") (pin "2") (pinfunction "2_2") (pintype "passive"))
      (node (ref "C20") (pin "2") (pinfunction "2_2") (pintype "passive"))
      (node (ref "C21") (pin "2") (pinfunction "2_2") (pintype "passive"))
      (node (ref "P8") (pin "9") (pinfunction "9_9") (pintype "passive"))
      (node (ref "Q1") (pin "1") (pinfunction "4_1") (pintype "passive"))
      (node (ref "Q1") (pin "4") (pinfunction "4_4") (pintype "passive"))
      (node (ref "Q2") (pin "1") (pinfunction "4_1") (pintype "passive"))
      (node (ref "Q2") (pin "4") (pinfunction "4_4") (pintype "passive"))
      (node (ref "Q3") (pin "1") (pinfunction "4_1") (pintype "passive"))
      (node (ref "Q3") (pin "4") (pinfunction "4_4") (pintype "passive"))
      (node (ref "R71") (pin "1") (pinfunction "1_1") (pintype "passive"))
      (node (ref "U10") (pin "13") (pinfunction "GND_13") (pintype "passive"))
      (node (ref "U10") (pin "16") (pinfunction "GND_16") (pintype "passive"))
      (node (ref "U10") (pin "2") (pinfunction "A0_2") (pintype "passive"))
      (node (ref "U10") (pin "3") (pinfunction "A1_3") (pintype "passive"))
      (node (ref "U10") (pin "4") (pinfunction "A2_4") (pintype "passive"))
      (node (ref "U10") (pin "5") (pinfunction "A3_5") (pintype "passive"))
      (node (ref "U10") (pin "8") (pinfunction "GND_8") (pintype "passive"))
      (node (ref "U11") (pin "11") (pinfunction "PAD_11") (pintype "passive"))
      (node (ref "U11") (pin "3") (pinfunction "GND_3") (pintype "passive"))
      (node (ref "U13") (pin "15") (pinfunction "GND_15") (pintype "passive"))
      (node (ref "U13") (pin "6") (pinfunction "A0_6") (pintype "passive"))
      (node (ref "U13") (pin "7") (pinfunction "A1_7") (pintype "passive"))
      (node (ref "U13") (pin "9") (pinfunction "A2_9") (pintype "passive"))
      (node (ref "U14") (pin "3") (pinfunction "GND_3") (pintype "passive"))
      (node (ref "U15") (pin "3") (pinfunction "GND_3") (pintype "passive"))
      (node (ref "U16") (pin "6") (pinfunction "GND_6") (pintype "passive"))
      (node (ref "U16") (pin "7") (pinfunction "GND_7") (pintype "passive"))
      (node (ref "U17") (pin "3") (pinfunction "GND_3") (pintype "passive"))
    )
    (net (code "51") (name "Net-(C19-Pad1)") (class "Default")
      (node (ref "C19") (pin "1") (pinfunction "1_1") (pintype "passive"))
      (node (ref "FB3") (pin "2") (pinfunction "2_2") (pintype "passive"))
      (node (ref "U16") (pin "13") (pinfunction "VCC_13") (pintype "passive"))
      (node (ref "U16") (pin "14") (pinfunction "VCC_14") (pintype "passive"))
    )
    (net (code "52") (name "Net-(C20-Pad1)") (class "Default")
      (node (ref "C20") (pin "1") (pinfunction "1_1") (pintype "passive"))
      (node (ref "R63") (pin "2") (pinfunction "2_2") (pintype "passive"))
      (node (ref "R65") (pin "2") (pinfunction "2_2") (pintype "passive"))
    )
    (net (code "53") (name "Net-(C21-Pad1)") (class "Default")
      (node (ref "C21") (pin "1") (pinfunction "1_1") (pintype "passive"))
      (node (ref "R67") (pin "2") (pinfunction "2_2") (pintype "passive"))
      (node (ref "R70") (pin "2") (pinfunction "2_2") (pintype "passive"))
    )
    (net (code "54") (name "Net-(Q1A-3)") (class "Default")
      (node (ref "Q1") (pin "6") (pinfunction "3_6") (pintype "passive"))
      (node (ref "U12") (pin "2") (pinfunction "-_2") (pintype "passive"))
    )
    (net (code "55") (name "Net-(U10-~{OUT0})") (class "Default")
      (node (ref "R36") (pin "1") (pinfunction "1_1") (pintype "passive"))
      (node (ref "U10") (pin "6") (pinfunction "~{OUT0}_6") (pintype "passive"))
    )
    (net (code "56") (name "Net-(U10-~{OUT1})") (class "Default")
      (node (ref "R37") (pin "1") (pinfunction "1_1") (pintype "passive"))
      (node (ref "U10") (pin "7") (pinfunction "~{OUT1}_7") (pintype "passive"))
    )
    (net (code "57") (name "Net-(U10-~{OUT2})") (class "Default")
      (node (ref "R38") (pin "1") (pinfunction "1_1") (pintype "passive"))
      (node (ref "U10") (pin "9") (pinfunction "~{OUT2}_9") (pintype "passive"))
    )
    (net (code "58") (name "Net-(U10-~{OUT3})") (class "Default")
      (node (ref "R39") (pin "1") (pinfunction "1_1") (pintype "passive"))
      (node (ref "U10") (pin "10") (pinfunction "~{OUT3}_10") (pintype "passive"))
    )
    (net (code "59") (name "Net-(U10-~{OUT4})") (class "Default")
      (node (ref "R40") (pin "1") (pinfunction "1_1") (pintype "passive"))
      (node (ref "U10") (pin "11") (pinfunction "~{OUT4}_11") (pintype "passive"))
    )
    (net (code "60") (name "Net-(U10-~{OUT5})") (class "Default")
      (node (ref "R42") (pin "1") (pinfunction "1_1") (pintype "passive"))
      (node (ref "U10") (pin "12") (pinfunction "~{OUT5}_12") (pintype "passive"))
    )
    (net (code "61") (name "Net-(U10-~{OUT6})") (class "Default")
      (node (ref "R43") (pin "1") (pinfunction "1_1") (pintype "passive"))
      (node (ref "U10") (pin "14") (pinfunction "~{OUT6}_14") (pintype "passive"))
    )
    (net (code "62") (name "Net-(U10-~{OUT7})") (class "Default")
      (node (ref "R44") (pin "1") (pinfunction "1_1") (pintype "passive"))
      (node (ref "U10") (pin "15") (pinfunction "~{OUT7}_15") (pintype "passive"))
    )
    (net (code "63") (name "Net-(U10-~{RESET})") (class "Default")
      (node (ref "R41") (pin "2") (pinfunction "2_2") (pintype "passive"))
      (node (ref "U10") (pin "17") (pinfunction "~{RESET}_17") (pintype "passive"))
    )
    (net (code "64") (name "Net-(U11-A0)") (class "Default")
      (node (ref "C16") (pin "2") (pinfunction "2_2") (pintype "passive"))
      (node (ref "FB2") (pin "2") (pinfunction "2_2") (pintype "passive"))
      (node (ref "U11") (pin "4") (pinfunction "VS_4") (pintype "passive"))
      (node (ref "U11") (pin "8") (pinfunction "A0_8") (pintype "passive"))
    )
    (net (code "65") (name "Net-(U12-+)") (class "Default")
      (node (ref "R45") (pin "2") (pinfunction "2_2") (pintype "passive"))
      (node (ref "U11") (pin "1") (pinfunction "VIN-_1") (pintype "passive"))
      (node (ref "U11") (pin "2") (pinfunction "VIN-_2") (pintype "passive"))
      (node (ref "U12") (pin "1") (pinfunction "+_1") (pintype "passive"))
    )
    (net (code "66") (name "Net-(U14-INT)") (class "Default")
      (node (ref "R61") (pin "1") (pinfunction "1_1") (pintype "passive"))
      (node (ref "U14") (pin "5") (pinfunction "INT_5") (pintype "passive"))
    )
    (net (code "67") (name "Net-(U16-A)") (class "Default")
      (node (ref "R62") (pin "2") (pinfunction "2_2") (pintype "passive"))
      (node (ref "U16") (pin "12") (pinfunction "A_12") (pintype "passive"))
    )
    (net (code "68") (name "Net-(U16-B)") (class "Default")
      (node (ref "R64") (pin "2") (pinfunction "2_2") (pintype "passive"))
      (node (ref "U16") (pin "11") (pinfunction "B_11") (pintype "passive"))
    )
    (net (code "69") (name "Net-(U16-Y)") (class "Default")
      (node (ref "R69") (pin "2") (pinfunction "2_2") (pintype "passive"))
      (node (ref "U16") (pin "9") (pinfunction "Y_9") (pintype "passive"))
    )
    (net (code "70") (name "Net-(U16-Z)") (class "Default")
      (node (ref "R66") (pin "2") (pinfunction "2_2") (pintype "passive"))
      (node (ref "U16") (pin "10") (pinfunction "Z_10") (pintype "passive"))
    )
    (net (code "71") (name "SYS_5V") (class "Default")
      (node (ref "C14") (pin "2") (pintype "passive"))
      (node (ref "R45") (pin "1") (pinfunction "1_1") (pintype "passive"))
      (node (ref "U11") (pin "10") (pinfunction "VIN+_10") (pintype "passive"))
      (node (ref "U11") (pin "9") (pinfunction "VIN+_9") (pintype "passive"))
    )
    (net (code "72") (name "VDD_3V3") (class "Default")
      (node (ref "FB2") (pin "1") (pinfunction "1_1") (pintype "passive"))
      (node (ref "FB3") (pin "1") (pinfunction "1_1") (pintype "passive"))
      (node (ref "R68") (pin "1") (pinfunction "1_1") (pintype "passive"))
      (node (ref "U14") (pin "1") (pinfunction "VDD_1") (pintype "passive"))
    )
    (net (code "73") (name "VDD_12V0") (class "Default")
      (node (ref "P7") (pin "1") (pinfunction "1_1") (pintype "passive"))
    )
    (net (code "74") (name "unconnected-(U10-NC-Pad1)") (class "Default")
      (node (ref "U10") (pin "1") (pinfunction "NC_1") (pintype "passive+no_connect"))
    )
    (net (code "75") (name "unconnected-(U13-NC-Pad3)") (class "Default")
      (node (ref "U13") (pin "3") (pinfunction "NC_3") (pintype "passive+no_connect"))
    )
    (net (code "76") (name "unconnected-(U13-NC-Pad8)") (class "Default")
      (node (ref "U13") (pin "8") (pinfunction "NC_8") (pintype "passive+no_connect"))
    )
    (net (code "77") (name "unconnected-(U13-NC-Pad13)") (class "Default")
      (node (ref "U13") (pin "13") (pinfunction "NC_13") (pintype "passive+no_connect"))
    )
    (net (code "78") (name "unconnected-(U13-NC-Pad18)") (class "Default")
      (node (ref "U13") (pin "18") (pinfunction "NC_18") (pintype "passive+no_connect"))
    )
    (net (code "79") (name "unconnected-(U13-~{INT}-Pad1)") (class "Default")
      (node (ref "U13") (pin "1") (pinfunction "~{INT}_1") (pintype "passive+no_connect"))
    )
    (net (code "80") (name "unconnected-(U14-NC-Pad2)") (class "Default")
      (node (ref "U14") (pin "2") (pinfunction "NC_2") (pintype "passive+no_connect"))
    )
    (net (code "81") (name "unconnected-(U16-NC-Pad1)") (class "Default")
      (node (ref "U16") (pin "1") (pinfunction "NC_1") (pintype "passive+no_connect"))
    )
    (net (code "82") (name "unconnected-(U16-NC-Pad8)") (class "Default")
      (node (ref "U16") (pin "8") (pinfunction "NC_8") (pintype "passive+no_connect"))
    )
  )
)
